# ARD_1_0.net
KiCad netlist of a schematic drawn in EAGLE
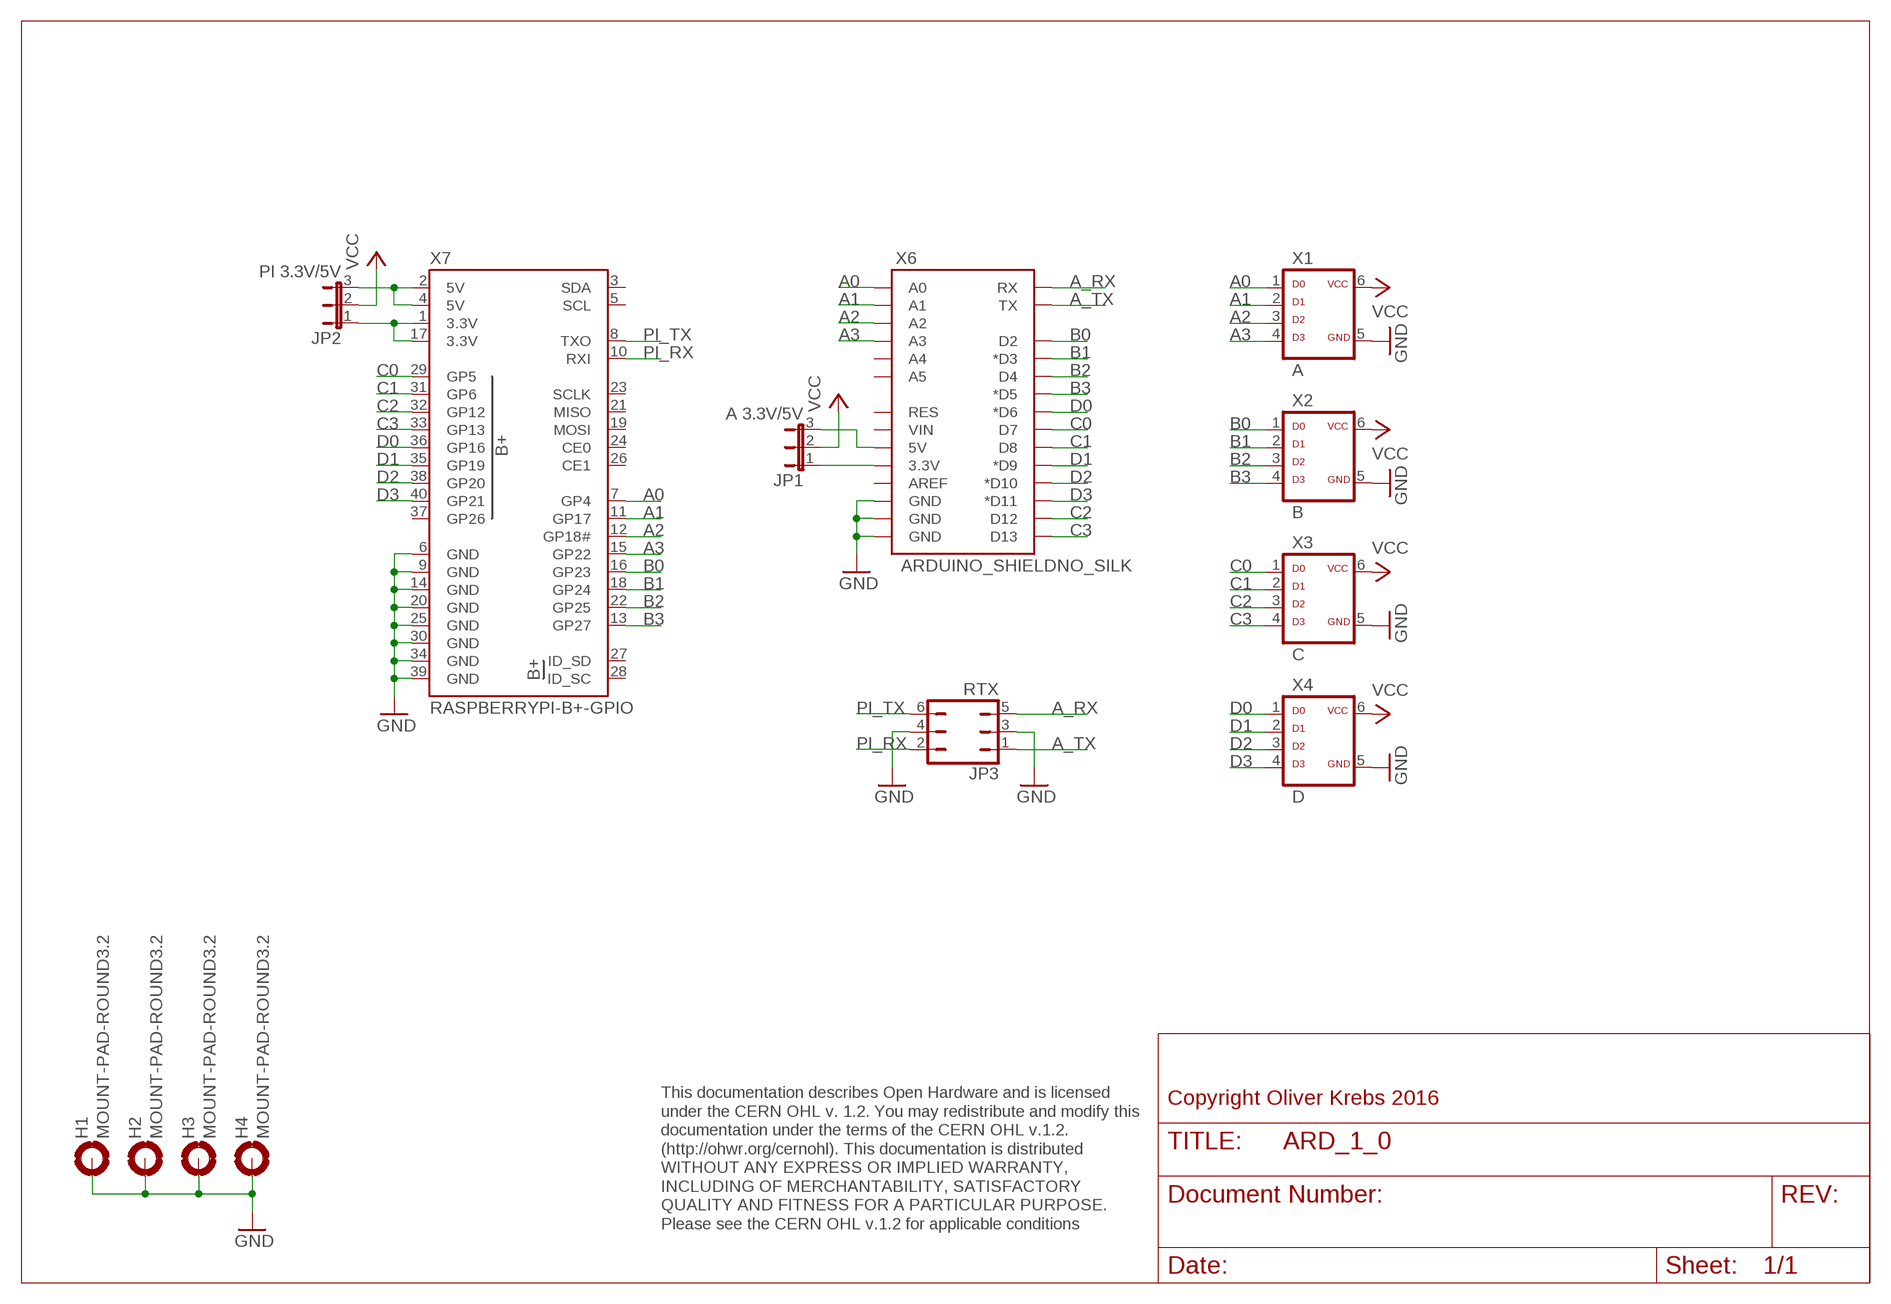
[diagram p0: schematic, sheet 1]

(export (version "E")
  (design (tool "Eeschema 10.0.6"))
  (components
    (comp (ref "H1")
      (value "MOUNT-PAD-ROUND3.2")
      (footprint "eagle-import:3,2-PAD")
      (libsource (lib "eagle-import") (part "MOUNT-PAD-ROUND3.2"))
    )
    (comp (ref "H2")
      (value "MOUNT-PAD-ROUND3.2")
      (footprint "eagle-import:3,2-PAD")
      (libsource (lib "eagle-import") (part "MOUNT-PAD-ROUND3.2"))
    )
    (comp (ref "H3")
      (value "MOUNT-PAD-ROUND3.2")
      (footprint "eagle-import:3,2-PAD")
      (libsource (lib "eagle-import") (part "MOUNT-PAD-ROUND3.2"))
    )
    (comp (ref "H4")
      (value "MOUNT-PAD-ROUND3.2")
      (footprint "eagle-import:3,2-PAD")
      (libsource (lib "eagle-import") (part "MOUNT-PAD-ROUND3.2"))
    )
    (comp (ref "JP1")
      (value "A 3.3V/5V")
      (footprint "eagle-import:JP2")
      (libsource (lib "eagle-import") (part "JP2E"))
    )
    (comp (ref "JP2")
      (value "PI 3.3V/5V")
      (footprint "eagle-import:JP2")
      (libsource (lib "eagle-import") (part "JP2E"))
    )
    (comp (ref "JP3")
      (value "RTX")
      (footprint "eagle-import:JP3Q")
      (libsource (lib "eagle-import") (part "JP3Q"))
    )
    (comp (ref "X1")
      (value "A")
      (footprint "eagle-import:ML-6")
      (libsource (lib "eagle-import") (part "ML6D"))
    )
    (comp (ref "X2")
      (value "B")
      (footprint "eagle-import:ML-6")
      (libsource (lib "eagle-import") (part "ML6D"))
    )
    (comp (ref "X3")
      (value "C")
      (footprint "eagle-import:ML-6")
      (libsource (lib "eagle-import") (part "ML6D"))
    )
    (comp (ref "X4")
      (value "D")
      (footprint "eagle-import:ML-6")
      (libsource (lib "eagle-import") (part "ML6D"))
    )
    (comp (ref "X6")
      (value "ARDUINO_SHIELDNO_SILK")
      (footprint "eagle-import:DUEMILANOVE_VIAS")
      (libsource (lib "eagle-import") (part "ARDUINO_SHIELDNO_SILK"))
    )
    (comp (ref "X7")
      (value "RASPBERRYPI-B+-GPIO")
      (footprint "eagle-import:2X20-SHROUDED")
      (libsource (lib "eagle-import") (part "RASPBERRYPI-B+-GPIO"))
    )
  )
  (nets
    (net (code "1") (name "/A0") (class "Default")
      (node (ref "X1") (pin "1") (pinfunction "1_1") (pintype "passive"))
      (node (ref "X6") (pin "A0") (pinfunction "A0_A0") (pintype "bidirectional"))
      (node (ref "X7") (pin "7") (pinfunction "GP4_7") (pintype "bidirectional"))
    )
    (net (code "2") (name "/A1") (class "Default")
      (node (ref "X1") (pin "2") (pinfunction "2_2") (pintype "passive"))
      (node (ref "X6") (pin "A1") (pinfunction "A1_A1") (pintype "bidirectional"))
      (node (ref "X7") (pin "11") (pinfunction "GP17_11") (pintype "bidirectional"))
    )
    (net (code "3") (name "/A2") (class "Default")
      (node (ref "X1") (pin "3") (pinfunction "3_3") (pintype "passive"))
      (node (ref "X6") (pin "A2") (pinfunction "A2_A2") (pintype "bidirectional"))
      (node (ref "X7") (pin "12") (pinfunction "GP18#_12") (pintype "bidirectional"))
    )
    (net (code "4") (name "/A3") (class "Default")
      (node (ref "X1") (pin "4") (pinfunction "4_4") (pintype "passive"))
      (node (ref "X6") (pin "A3") (pinfunction "A3_A3") (pintype "bidirectional"))
      (node (ref "X7") (pin "15") (pinfunction "GP22_15") (pintype "bidirectional"))
    )
    (net (code "5") (name "/A_RX") (class "Default")
      (node (ref "JP3") (pin "5") (pinfunction "5_5") (pintype "passive"))
      (node (ref "X6") (pin "RX") (pinfunction "RX_RX") (pintype "bidirectional"))
    )
    (net (code "6") (name "/A_TX") (class "Default")
      (node (ref "JP3") (pin "1") (pinfunction "1_1") (pintype "passive"))
      (node (ref "X6") (pin "TX") (pinfunction "TX_TX") (pintype "bidirectional"))
    )
    (net (code "7") (name "/B0") (class "Default")
      (node (ref "X2") (pin "1") (pinfunction "1_1") (pintype "passive"))
      (node (ref "X6") (pin "D2") (pinfunction "D2_D2") (pintype "bidirectional"))
      (node (ref "X7") (pin "16") (pinfunction "GP23_16") (pintype "bidirectional"))
    )
    (net (code "8") (name "/B1") (class "Default")
      (node (ref "X2") (pin "2") (pinfunction "2_2") (pintype "passive"))
      (node (ref "X6") (pin "D3") (pinfunction "*D3_D3") (pintype "bidirectional"))
      (node (ref "X7") (pin "18") (pinfunction "GP24_18") (pintype "bidirectional"))
    )
    (net (code "9") (name "/B2") (class "Default")
      (node (ref "X2") (pin "3") (pinfunction "3_3") (pintype "passive"))
      (node (ref "X6") (pin "D4") (pinfunction "D4_D4") (pintype "bidirectional"))
      (node (ref "X7") (pin "22") (pinfunction "GP25_22") (pintype "bidirectional"))
    )
    (net (code "10") (name "/B3") (class "Default")
      (node (ref "X2") (pin "4") (pinfunction "4_4") (pintype "passive"))
      (node (ref "X6") (pin "D5") (pinfunction "*D5_D5") (pintype "bidirectional"))
      (node (ref "X7") (pin "13") (pinfunction "GP27_13") (pintype "bidirectional"))
    )
    (net (code "11") (name "/C0") (class "Default")
      (node (ref "X3") (pin "1") (pinfunction "1_1") (pintype "passive"))
      (node (ref "X6") (pin "D7") (pinfunction "D7_D7") (pintype "bidirectional"))
      (node (ref "X7") (pin "29") (pinfunction "GP5_29") (pintype "bidirectional"))
    )
    (net (code "12") (name "/C1") (class "Default")
      (node (ref "X3") (pin "2") (pinfunction "2_2") (pintype "passive"))
      (node (ref "X6") (pin "D8") (pinfunction "D8_D8") (pintype "bidirectional"))
      (node (ref "X7") (pin "31") (pinfunction "GP6_31") (pintype "bidirectional"))
    )
    (net (code "13") (name "/C2") (class "Default")
      (node (ref "X3") (pin "3") (pinfunction "3_3") (pintype "passive"))
      (node (ref "X6") (pin "D12") (pinfunction "D12_D12") (pintype "bidirectional"))
      (node (ref "X7") (pin "32") (pinfunction "GP12_32") (pintype "bidirectional"))
    )
    (net (code "14") (name "/C3") (class "Default")
      (node (ref "X3") (pin "4") (pinfunction "4_4") (pintype "passive"))
      (node (ref "X6") (pin "D13") (pinfunction "D13_D13") (pintype "bidirectional"))
      (node (ref "X7") (pin "33") (pinfunction "GP13_33") (pintype "bidirectional"))
    )
    (net (code "15") (name "/D0") (class "Default")
      (node (ref "X4") (pin "1") (pinfunction "1_1") (pintype "passive"))
      (node (ref "X6") (pin "D6") (pinfunction "*D6_D6") (pintype "bidirectional"))
      (node (ref "X7") (pin "36") (pinfunction "GP16_36") (pintype "bidirectional"))
    )
    (net (code "16") (name "/D1") (class "Default")
      (node (ref "X4") (pin "2") (pinfunction "2_2") (pintype "passive"))
      (node (ref "X6") (pin "D9") (pinfunction "*D9_D9") (pintype "bidirectional"))
      (node (ref "X7") (pin "35") (pinfunction "GP19_35") (pintype "bidirectional"))
    )
    (net (code "17") (name "/D2") (class "Default")
      (node (ref "X4") (pin "3") (pinfunction "3_3") (pintype "passive"))
      (node (ref "X6") (pin "D10") (pinfunction "*D10_D10") (pintype "bidirectional"))
      (node (ref "X7") (pin "38") (pinfunction "GP20_38") (pintype "bidirectional"))
    )
    (net (code "18") (name "/D3") (class "Default")
      (node (ref "X4") (pin "4") (pinfunction "4_4") (pintype "passive"))
      (node (ref "X6") (pin "D11") (pinfunction "*D11_D11") (pintype "bidirectional"))
      (node (ref "X7") (pin "40") (pinfunction "GP21_40") (pintype "bidirectional"))
    )
    (net (code "19") (name "/PI_RX") (class "Default")
      (node (ref "JP3") (pin "2") (pinfunction "2_2") (pintype "passive"))
      (node (ref "X7") (pin "10") (pinfunction "RXI_10") (pintype "input"))
    )
    (net (code "20") (name "/PI_TX") (class "Default")
      (node (ref "JP3") (pin "6") (pinfunction "6_6") (pintype "passive"))
      (node (ref "X7") (pin "8") (pinfunction "TXO_8") (pintype "output"))
    )
    (net (code "21") (name "GND") (class "Default")
      (node (ref "H1") (pin "B3,2") (pinfunction "MOUNT_B3,2") (pintype "passive"))
      (node (ref "H2") (pin "B3,2") (pinfunction "MOUNT_B3,2") (pintype "passive"))
      (node (ref "H3") (pin "B3,2") (pinfunction "MOUNT_B3,2") (pintype "passive"))
      (node (ref "H4") (pin "B3,2") (pinfunction "MOUNT_B3,2") (pintype "passive"))
      (node (ref "JP3") (pin "3") (pinfunction "3_3") (pintype "passive"))
      (node (ref "JP3") (pin "4") (pinfunction "4_4") (pintype "passive"))
      (node (ref "X1") (pin "5") (pinfunction "5_5") (pintype "passive"))
      (node (ref "X2") (pin "5") (pinfunction "5_5") (pintype "passive"))
      (node (ref "X3") (pin "5") (pinfunction "5_5") (pintype "passive"))
      (node (ref "X4") (pin "5") (pinfunction "5_5") (pintype "passive"))
      (node (ref "X6") (pin "GND@0") (pinfunction "GND_GND@0") (pintype "bidirectional"))
      (node (ref "X6") (pin "GND@1") (pinfunction "GND_GND@1") (pintype "bidirectional"))
      (node (ref "X6") (pin "GND@2") (pinfunction "GND_GND@2") (pintype "bidirectional"))
      (node (ref "X7") (pin "14") (pinfunction "GND_14") (pintype "power_in"))
      (node (ref "X7") (pin "20") (pinfunction "GND_20") (pintype "power_in"))
      (node (ref "X7") (pin "25") (pinfunction "GND_25") (pintype "power_in"))
      (node (ref "X7") (pin "30") (pinfunction "GND_30") (pintype "power_in"))
      (node (ref "X7") (pin "34") (pinfunction "GND_34") (pintype "power_in"))
      (node (ref "X7") (pin "39") (pinfunction "GND_39") (pintype "power_in"))
      (node (ref "X7") (pin "6") (pinfunction "GND_6") (pintype "power_in"))
      (node (ref "X7") (pin "9") (pinfunction "GND_9") (pintype "power_in"))
    )
    (net (code "22") (name "Net-(JP1-Pad1)") (class "Default")
      (node (ref "JP1") (pin "1") (pinfunction "1_1") (pintype "passive"))
      (node (ref "X6") (pin "3.3V") (pinfunction "3.3V_3.3V") (pintype "bidirectional"))
    )
    (net (code "23") (name "Net-(JP1-Pad3)") (class "Default")
      (node (ref "JP1") (pin "3") (pinfunction "3_3") (pintype "passive"))
      (node (ref "X6") (pin "5V") (pinfunction "5V_5V") (pintype "bidirectional"))
    )
    (net (code "24") (name "Net-(JP2-Pad1)") (class "Default")
      (node (ref "JP2") (pin "1") (pinfunction "1_1") (pintype "passive"))
      (node (ref "X7") (pin "1") (pinfunction "3.3V_1") (pintype "power_in"))
      (node (ref "X7") (pin "17") (pinfunction "3.3V_17") (pintype "power_in"))
    )
    (net (code "25") (name "Net-(JP2-Pad3)") (class "Default")
      (node (ref "JP2") (pin "3") (pinfunction "3_3") (pintype "passive"))
      (node (ref "X7") (pin "2") (pinfunction "5V_2") (pintype "power_in"))
      (node (ref "X7") (pin "4") (pinfunction "5V_4") (pintype "power_in"))
    )
    (net (code "26") (name "VCC") (class "Default")
      (node (ref "JP1") (pin "2") (pinfunction "2_2") (pintype "passive"))
      (node (ref "JP2") (pin "2") (pinfunction "2_2") (pintype "passive"))
      (node (ref "X1") (pin "6") (pinfunction "6_6") (pintype "passive"))
      (node (ref "X2") (pin "6") (pinfunction "6_6") (pintype "passive"))
      (node (ref "X3") (pin "6") (pinfunction "6_6") (pintype "passive"))
      (node (ref "X4") (pin "6") (pinfunction "6_6") (pintype "passive"))
    )
    (net (code "27") (name "unconnected-(X6-PadA4)") (class "Default")
      (node (ref "X6") (pin "A4") (pinfunction "A4_A4") (pintype "bidirectional"))
    )
    (net (code "28") (name "unconnected-(X6-PadA5)") (class "Default")
      (node (ref "X6") (pin "A5") (pinfunction "A5_A5") (pintype "bidirectional"))
    )
    (net (code "29") (name "unconnected-(X6-PadAREF)") (class "Default")
      (node (ref "X6") (pin "AREF") (pinfunction "AREF_AREF") (pintype "bidirectional"))
    )
    (net (code "30") (name "unconnected-(X6-PadRES)") (class "Default")
      (node (ref "X6") (pin "RES") (pinfunction "RES_RES") (pintype "bidirectional"))
    )
    (net (code "31") (name "unconnected-(X6-PadVIN)") (class "Default")
      (node (ref "X6") (pin "VIN") (pinfunction "VIN_VIN") (pintype "bidirectional"))
    )
    (net (code "32") (name "unconnected-(X7-CE0-Pad24)") (class "Default")
      (node (ref "X7") (pin "24") (pinfunction "CE0_24") (pintype "output"))
    )
    (net (code "33") (name "unconnected-(X7-CE1-Pad26)") (class "Default")
      (node (ref "X7") (pin "26") (pinfunction "CE1_26") (pintype "output"))
    )
    (net (code "34") (name "unconnected-(X7-GP26-Pad37)") (class "Default")
      (node (ref "X7") (pin "37") (pinfunction "GP26_37") (pintype "bidirectional"))
    )
    (net (code "35") (name "unconnected-(X7-ID_SC-Pad28)") (class "Default")
      (node (ref "X7") (pin "28") (pinfunction "ID_SC_28") (pintype "bidirectional"))
    )
    (net (code "36") (name "unconnected-(X7-ID_SD-Pad27)") (class "Default")
      (node (ref "X7") (pin "27") (pinfunction "ID_SD_27") (pintype "bidirectional"))
    )
    (net (code "37") (name "unconnected-(X7-MISO-Pad21)") (class "Default")
      (node (ref "X7") (pin "21") (pinfunction "MISO_21") (pintype "input"))
    )
    (net (code "38") (name "unconnected-(X7-MOSI-Pad19)") (class "Default")
      (node (ref "X7") (pin "19") (pinfunction "MOSI_19") (pintype "output"))
    )
    (net (code "39") (name "unconnected-(X7-SCL-Pad5)") (class "Default")
      (node (ref "X7") (pin "5") (pinfunction "SCL_5") (pintype "bidirectional"))
    )
    (net (code "40") (name "unconnected-(X7-SCLK-Pad23)") (class "Default")
      (node (ref "X7") (pin "23") (pinfunction "SCLK_23") (pintype "output"))
    )
    (net (code "41") (name "unconnected-(X7-SDA-Pad3)") (class "Default")
      (node (ref "X7") (pin "3") (pinfunction "SDA_3") (pintype "bidirectional"))
    )
  )
)
